# RATS_Schematic.net
KiCad netlist of a schematic drawn in EAGLE
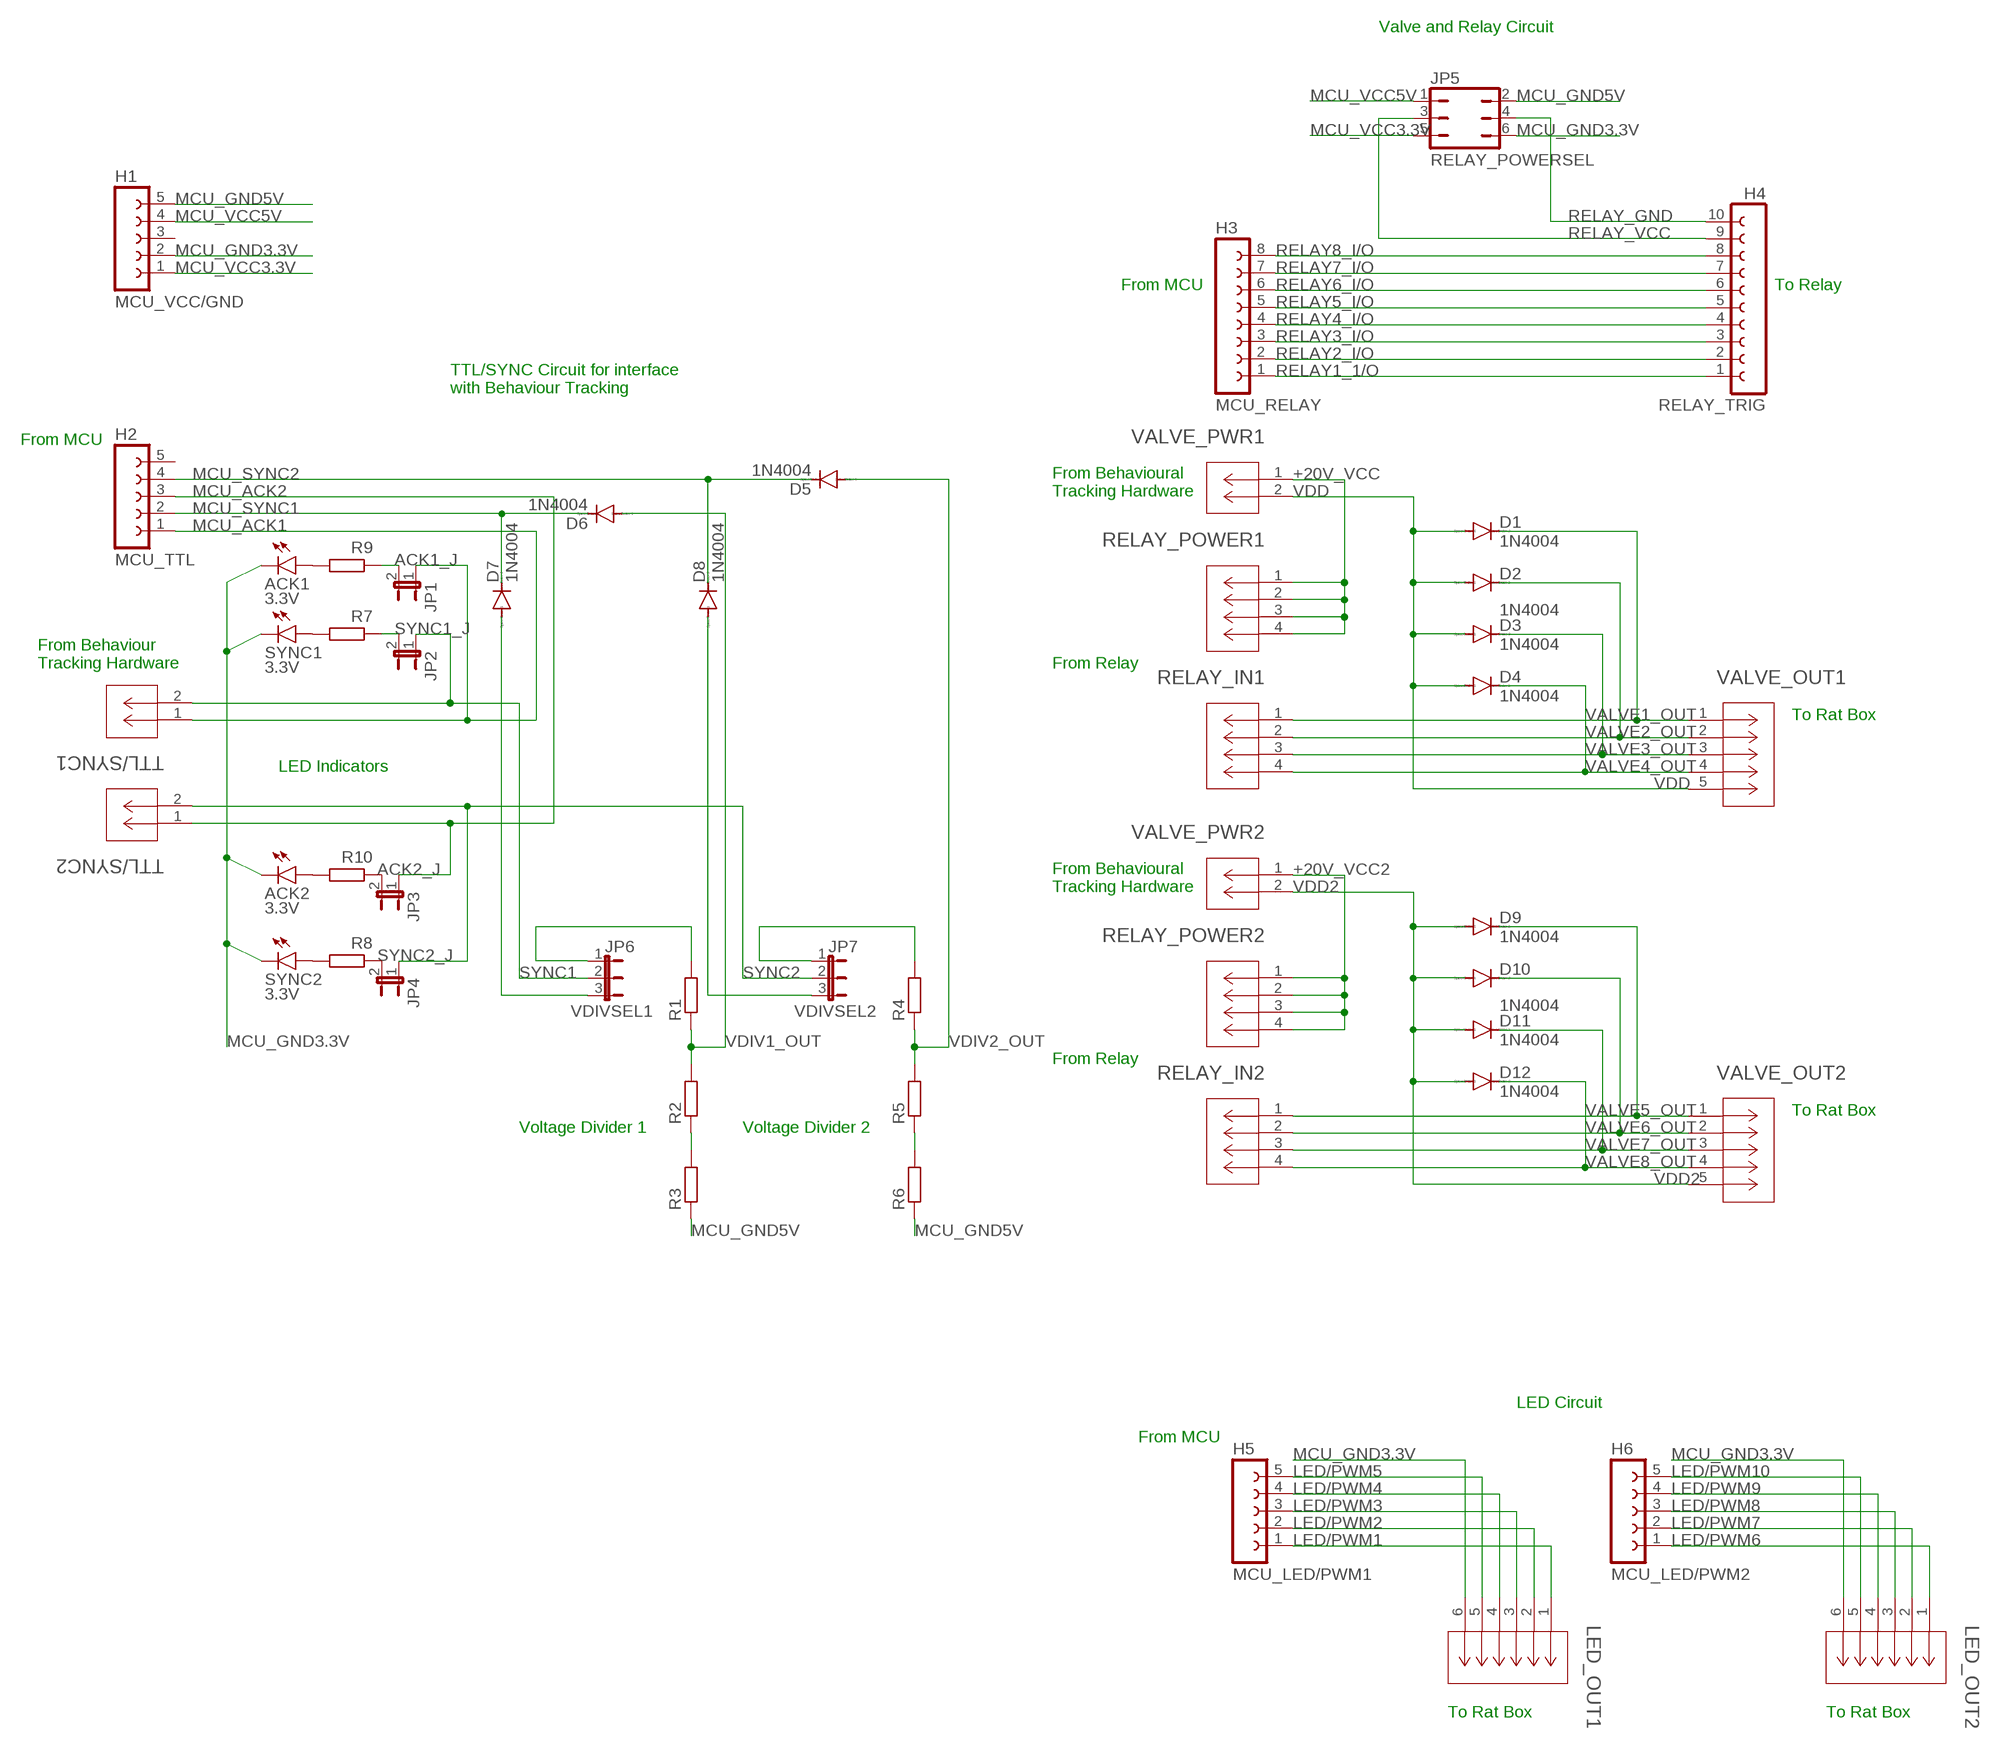
[diagram p0: schematic, sheet 1]

(export (version "E")
  (design (tool "Eeschema 10.0.6"))
  (components
    (comp (ref "ACK1")
      (value "3.3V")
      (footprint "eagle-import:LED5MM")
      (libsource (lib "eagle-import") (part "LED5MM"))
    )
    (comp (ref "ACK2")
      (value "3.3V")
      (footprint "eagle-import:LED5MM")
      (libsource (lib "eagle-import") (part "LED5MM"))
    )
    (comp (ref "D1")
      (value "1N4004")
      (footprint "eagle-import:DO41-10")
      (libsource (lib "eagle-import") (part "1N4004"))
    )
    (comp (ref "D2")
      (value "1N4004")
      (footprint "eagle-import:DO41-10")
      (libsource (lib "eagle-import") (part "1N4004"))
    )
    (comp (ref "D3")
      (value "1N4004")
      (footprint "eagle-import:DO41-10")
      (libsource (lib "eagle-import") (part "1N4004"))
    )
    (comp (ref "D4")
      (value "1N4004")
      (footprint "eagle-import:DO41-10")
      (libsource (lib "eagle-import") (part "1N4004"))
    )
    (comp (ref "D5")
      (value "1N4004")
      (footprint "eagle-import:DO41-10")
      (libsource (lib "eagle-import") (part "1N4004"))
    )
    (comp (ref "D6")
      (value "1N4004")
      (footprint "eagle-import:DO41-10")
      (libsource (lib "eagle-import") (part "1N4004"))
    )
    (comp (ref "D7")
      (value "1N4004")
      (footprint "eagle-import:DO41-10")
      (libsource (lib "eagle-import") (part "1N4004"))
    )
    (comp (ref "D8")
      (value "1N4004")
      (footprint "eagle-import:DO41-10")
      (libsource (lib "eagle-import") (part "1N4004"))
    )
    (comp (ref "D9")
      (value "1N4004")
      (footprint "eagle-import:DO41-10")
      (libsource (lib "eagle-import") (part "1N4004"))
    )
    (comp (ref "D10")
      (value "1N4004")
      (footprint "eagle-import:DO41-10")
      (libsource (lib "eagle-import") (part "1N4004"))
    )
    (comp (ref "D11")
      (value "1N4004")
      (footprint "eagle-import:DO41-10")
      (libsource (lib "eagle-import") (part "1N4004"))
    )
    (comp (ref "D12")
      (value "1N4004")
      (footprint "eagle-import:DO41-10")
      (libsource (lib "eagle-import") (part "1N4004"))
    )
    (comp (ref "H1")
      (value "MCU_VCC/GND")
      (footprint "eagle-import:FE05-1")
      (libsource (lib "eagle-import") (part "FE05-1"))
    )
    (comp (ref "H2")
      (value "MCU_TTL")
      (footprint "eagle-import:FE05-1")
      (libsource (lib "eagle-import") (part "FE05-1"))
    )
    (comp (ref "H3")
      (value "MCU_RELAY")
      (footprint "eagle-import:FE08")
      (libsource (lib "eagle-import") (part "FE08-1"))
    )
    (comp (ref "H4")
      (value "RELAY_TRIG")
      (footprint "eagle-import:FE10")
      (libsource (lib "eagle-import") (part "FE10-1"))
    )
    (comp (ref "H5")
      (value "MCU_LED/PWM1")
      (footprint "eagle-import:FE05-1")
      (libsource (lib "eagle-import") (part "FE05-1"))
    )
    (comp (ref "H6")
      (value "MCU_LED/PWM2")
      (footprint "eagle-import:FE05-1")
      (libsource (lib "eagle-import") (part "FE05-1"))
    )
    (comp (ref "JP1")
      (value "ACK1_J")
      (footprint "eagle-import:JP1")
      (libsource (lib "eagle-import") (part "JP1E"))
    )
    (comp (ref "JP2")
      (value "SYNC1_J")
      (footprint "eagle-import:JP1")
      (libsource (lib "eagle-import") (part "JP1E"))
    )
    (comp (ref "JP3")
      (value "ACK2_J")
      (footprint "eagle-import:JP1")
      (libsource (lib "eagle-import") (part "JP1E"))
    )
    (comp (ref "JP4")
      (value "SYNC2_J")
      (footprint "eagle-import:JP1")
      (libsource (lib "eagle-import") (part "JP1E"))
    )
    (comp (ref "JP5")
      (value "RELAY_POWERSEL")
      (footprint "eagle-import:JP3Q")
      (libsource (lib "eagle-import") (part "JP3Q"))
    )
    (comp (ref "JP6")
      (value "VDIVSEL1")
      (footprint "eagle-import:JP2")
      (libsource (lib "eagle-import") (part "JP2E"))
    )
    (comp (ref "JP7")
      (value "VDIVSEL2")
      (footprint "eagle-import:JP2")
      (libsource (lib "eagle-import") (part "JP2E"))
    )
    (comp (ref "LED_OUT1")
      (value "B6B-XH-A(LF)(SN)")
      (footprint "eagle-import:CONN_B6B-XH-A(LF)(SN)_JST")
      (fields (field (name "COPYRIGHT") "Copyright (C) 2021 Ultra Librarian. All rights reserved."))
      (libsource (lib "eagle-import") (part "B6B-XH-A(LF)(SN)"))
    )
    (comp (ref "LED_OUT2")
      (value "B6B-XH-A(LF)(SN)")
      (footprint "eagle-import:CONN_B6B-XH-A(LF)(SN)_JST")
      (fields (field (name "COPYRIGHT") "Copyright (C) 2021 Ultra Librarian. All rights reserved."))
      (libsource (lib "eagle-import") (part "B6B-XH-A(LF)(SN)"))
    )
    (comp (ref "R1")
      (value "R-EU_0204/7")
      (footprint "eagle-import:0204_7")
      (libsource (lib "eagle-import") (part "R-EU_0204/7"))
    )
    (comp (ref "R2")
      (value "R-EU_0204/7")
      (footprint "eagle-import:0204_7")
      (libsource (lib "eagle-import") (part "R-EU_0204/7"))
    )
    (comp (ref "R3")
      (value "R-EU_0204/7")
      (footprint "eagle-import:0204_7")
      (libsource (lib "eagle-import") (part "R-EU_0204/7"))
    )
    (comp (ref "R4")
      (value "R-EU_0204/7")
      (footprint "eagle-import:0204_7")
      (libsource (lib "eagle-import") (part "R-EU_0204/7"))
    )
    (comp (ref "R5")
      (value "R-EU_0204/7")
      (footprint "eagle-import:0204_7")
      (libsource (lib "eagle-import") (part "R-EU_0204/7"))
    )
    (comp (ref "R6")
      (value "R-EU_0204/7")
      (footprint "eagle-import:0204_7")
      (libsource (lib "eagle-import") (part "R-EU_0204/7"))
    )
    (comp (ref "R7")
      (value "R-EU_0204/7")
      (footprint "eagle-import:0204_7")
      (libsource (lib "eagle-import") (part "R-EU_0204/7"))
    )
    (comp (ref "R8")
      (value "R-EU_0204/7")
      (footprint "eagle-import:0204_7")
      (libsource (lib "eagle-import") (part "R-EU_0204/7"))
    )
    (comp (ref "R9")
      (value "R-EU_0204/7")
      (footprint "eagle-import:0204_7")
      (libsource (lib "eagle-import") (part "R-EU_0204/7"))
    )
    (comp (ref "R10")
      (value "R-EU_0204/7")
      (footprint "eagle-import:0204_7")
      (libsource (lib "eagle-import") (part "R-EU_0204/7"))
    )
    (comp (ref "RELAY_IN1")
      (value "B4B-XH-A_(LF)(SN)")
      (footprint "eagle-import:CONN_B4B-XH-A_(LF)(SN)_JST")
      (fields
        (field (name "MANUFACTURER_PART_NUMBER") "B4B-XH-A (LF)(SN)")
        (field (name "COPYRIGHT") "Copyright (C) 2021 Ultra Librarian. All rights reserved.")
      )
      (libsource (lib "eagle-import") (part "B4B-XH-A_(LF)(SN)"))
    )
    (comp (ref "RELAY_IN2")
      (value "B4B-XH-A_(LF)(SN)")
      (footprint "eagle-import:CONN_B4B-XH-A_(LF)(SN)_JST")
      (fields
        (field (name "MANUFACTURER_PART_NUMBER") "B4B-XH-A (LF)(SN)")
        (field (name "COPYRIGHT") "Copyright (C) 2021 Ultra Librarian. All rights reserved.")
      )
      (libsource (lib "eagle-import") (part "B4B-XH-A_(LF)(SN)"))
    )
    (comp (ref "RELAY_POWER1")
      (value "B4B-XH-A_(LF)(SN)")
      (footprint "eagle-import:CONN_B4B-XH-A_(LF)(SN)_JST")
      (fields
        (field (name "MANUFACTURER_PART_NUMBER") "B4B-XH-A (LF)(SN)")
        (field (name "COPYRIGHT") "Copyright (C) 2021 Ultra Librarian. All rights reserved.")
      )
      (libsource (lib "eagle-import") (part "B4B-XH-A_(LF)(SN)"))
    )
    (comp (ref "RELAY_POWER2")
      (value "B4B-XH-A_(LF)(SN)")
      (footprint "eagle-import:CONN_B4B-XH-A_(LF)(SN)_JST")
      (fields
        (field (name "MANUFACTURER_PART_NUMBER") "B4B-XH-A (LF)(SN)")
        (field (name "COPYRIGHT") "Copyright (C) 2021 Ultra Librarian. All rights reserved.")
      )
      (libsource (lib "eagle-import") (part "B4B-XH-A_(LF)(SN)"))
    )
    (comp (ref "SYNC1")
      (value "3.3V")
      (footprint "eagle-import:LED5MM")
      (libsource (lib "eagle-import") (part "LED5MM"))
    )
    (comp (ref "SYNC2")
      (value "3.3V")
      (footprint "eagle-import:LED5MM")
      (libsource (lib "eagle-import") (part "LED5MM"))
    )
    (comp (ref "TTL/SYNC1")
      (value "B2B-XH-A(LF)(SN)")
      (footprint "eagle-import:CONN_B2B-XH-A(LF)(SN)_JST")
      (fields (field (name "COPYRIGHT") "Copyright (C) 2021 Ultra Librarian. All rights reserved."))
      (libsource (lib "eagle-import") (part "B2B-XH-A(LF)(SN)"))
    )
    (comp (ref "TTL/SYNC2")
      (value "B2B-XH-A(LF)(SN)")
      (footprint "eagle-import:CONN_B2B-XH-A(LF)(SN)_JST")
      (fields (field (name "COPYRIGHT") "Copyright (C) 2021 Ultra Librarian. All rights reserved."))
      (libsource (lib "eagle-import") (part "B2B-XH-A(LF)(SN)"))
    )
    (comp (ref "VALVE_OUT1")
      (value "B5B-XH-A(LF)(SN)")
      (footprint "eagle-import:CONN_B5B-XH-A(LF)(SN)_JST")
      (fields (field (name "COPYRIGHT") "Copyright (C) 2021 Ultra Librarian. All rights reserved."))
      (libsource (lib "eagle-import") (part "B5B-XH-A(LF)(SN)"))
    )
    (comp (ref "VALVE_OUT2")
      (value "B5B-XH-A(LF)(SN)")
      (footprint "eagle-import:CONN_B5B-XH-A(LF)(SN)_JST")
      (fields (field (name "COPYRIGHT") "Copyright (C) 2021 Ultra Librarian. All rights reserved."))
      (libsource (lib "eagle-import") (part "B5B-XH-A(LF)(SN)"))
    )
    (comp (ref "VALVE_PWR1")
      (value "B2B-XH-A(LF)(SN)")
      (footprint "eagle-import:CONN_B2B-XH-A(LF)(SN)_JST")
      (fields (field (name "COPYRIGHT") "Copyright (C) 2021 Ultra Librarian. All rights reserved."))
      (libsource (lib "eagle-import") (part "B2B-XH-A(LF)(SN)"))
    )
    (comp (ref "VALVE_PWR2")
      (value "B2B-XH-A(LF)(SN)")
      (footprint "eagle-import:CONN_B2B-XH-A(LF)(SN)_JST")
      (fields (field (name "COPYRIGHT") "Copyright (C) 2021 Ultra Librarian. All rights reserved."))
      (libsource (lib "eagle-import") (part "B2B-XH-A(LF)(SN)"))
    )
  )
  (nets
    (net (code "1") (name "/+20V_VCC") (class "Default")
      (node (ref "RELAY_POWER1") (pin "1") (pinfunction "1_1") (pintype "passive"))
      (node (ref "RELAY_POWER1") (pin "2") (pinfunction "2_2") (pintype "passive"))
      (node (ref "RELAY_POWER1") (pin "3") (pinfunction "3_3") (pintype "passive"))
      (node (ref "RELAY_POWER1") (pin "4") (pinfunction "4_4") (pintype "passive"))
      (node (ref "VALVE_PWR1") (pin "1") (pinfunction "1_1") (pintype "passive"))
    )
    (net (code "2") (name "/+20V_VCC2") (class "Default")
      (node (ref "RELAY_POWER2") (pin "1") (pinfunction "1_1") (pintype "passive"))
      (node (ref "RELAY_POWER2") (pin "2") (pinfunction "2_2") (pintype "passive"))
      (node (ref "RELAY_POWER2") (pin "3") (pinfunction "3_3") (pintype "passive"))
      (node (ref "RELAY_POWER2") (pin "4") (pinfunction "4_4") (pintype "passive"))
      (node (ref "VALVE_PWR2") (pin "1") (pinfunction "1_1") (pintype "passive"))
    )
    (net (code "3") (name "/LED{slash}PWM1") (class "Default")
      (node (ref "H5") (pin "1") (pinfunction "1_1") (pintype "passive"))
      (node (ref "LED_OUT1") (pin "1") (pinfunction "1_1") (pintype "passive"))
    )
    (net (code "4") (name "/LED{slash}PWM2") (class "Default")
      (node (ref "H5") (pin "2") (pinfunction "2_2") (pintype "passive"))
      (node (ref "LED_OUT1") (pin "2") (pinfunction "2_2") (pintype "passive"))
    )
    (net (code "5") (name "/LED{slash}PWM3") (class "Default")
      (node (ref "H5") (pin "3") (pinfunction "3_3") (pintype "passive"))
      (node (ref "LED_OUT1") (pin "3") (pinfunction "3_3") (pintype "passive"))
    )
    (net (code "6") (name "/LED{slash}PWM4") (class "Default")
      (node (ref "H5") (pin "4") (pinfunction "4_4") (pintype "passive"))
      (node (ref "LED_OUT1") (pin "4") (pinfunction "4_4") (pintype "passive"))
    )
    (net (code "7") (name "/LED{slash}PWM5") (class "Default")
      (node (ref "H5") (pin "5") (pinfunction "5_5") (pintype "passive"))
      (node (ref "LED_OUT1") (pin "5") (pinfunction "5_5") (pintype "passive"))
    )
    (net (code "8") (name "/LED{slash}PWM6") (class "Default")
      (node (ref "H6") (pin "1") (pinfunction "1_1") (pintype "passive"))
      (node (ref "LED_OUT2") (pin "1") (pinfunction "1_1") (pintype "passive"))
    )
    (net (code "9") (name "/LED{slash}PWM7") (class "Default")
      (node (ref "H6") (pin "2") (pinfunction "2_2") (pintype "passive"))
      (node (ref "LED_OUT2") (pin "2") (pinfunction "2_2") (pintype "passive"))
    )
    (net (code "10") (name "/LED{slash}PWM8") (class "Default")
      (node (ref "H6") (pin "3") (pinfunction "3_3") (pintype "passive"))
      (node (ref "LED_OUT2") (pin "3") (pinfunction "3_3") (pintype "passive"))
    )
    (net (code "11") (name "/LED{slash}PWM9") (class "Default")
      (node (ref "H6") (pin "4") (pinfunction "4_4") (pintype "passive"))
      (node (ref "LED_OUT2") (pin "4") (pinfunction "4_4") (pintype "passive"))
    )
    (net (code "12") (name "/LED{slash}PWM10") (class "Default")
      (node (ref "H6") (pin "5") (pinfunction "5_5") (pintype "passive"))
      (node (ref "LED_OUT2") (pin "5") (pinfunction "5_5") (pintype "passive"))
    )
    (net (code "13") (name "/MCU_ACK1") (class "Default")
      (node (ref "H2") (pin "1") (pinfunction "1_1") (pintype "passive"))
      (node (ref "JP1") (pin "1") (pinfunction "1_1") (pintype "passive"))
      (node (ref "TTL/SYNC1") (pin "1") (pinfunction "1_1") (pintype "passive"))
    )
    (net (code "14") (name "/MCU_ACK2") (class "Default")
      (node (ref "H2") (pin "3") (pinfunction "3_3") (pintype "passive"))
      (node (ref "JP3") (pin "1") (pinfunction "1_1") (pintype "passive"))
      (node (ref "TTL/SYNC2") (pin "1") (pinfunction "1_1") (pintype "passive"))
    )
    (net (code "15") (name "/MCU_GND3.3V") (class "Default")
      (node (ref "ACK1") (pin "K") (pinfunction "C_K") (pintype "passive"))
      (node (ref "ACK2") (pin "K") (pinfunction "C_K") (pintype "passive"))
      (node (ref "H1") (pin "2") (pinfunction "2_2") (pintype "passive"))
      (node (ref "JP5") (pin "6") (pinfunction "6_6") (pintype "passive"))
      (node (ref "LED_OUT1") (pin "6") (pinfunction "6_6") (pintype "passive"))
      (node (ref "LED_OUT2") (pin "6") (pinfunction "6_6") (pintype "passive"))
      (node (ref "SYNC1") (pin "K") (pinfunction "C_K") (pintype "passive"))
      (node (ref "SYNC2") (pin "K") (pinfunction "C_K") (pintype "passive"))
    )
    (net (code "16") (name "/MCU_GND5V") (class "Default")
      (node (ref "H1") (pin "5") (pinfunction "5_5") (pintype "passive"))
      (node (ref "JP5") (pin "2") (pinfunction "2_2") (pintype "passive"))
      (node (ref "R3") (pin "1") (pinfunction "1_1") (pintype "passive"))
      (node (ref "R6") (pin "1") (pinfunction "1_1") (pintype "passive"))
    )
    (net (code "17") (name "/MCU_SYNC1") (class "Default")
      (node (ref "D6") (pin "C") (pinfunction "C_C") (pintype "passive"))
      (node (ref "D7") (pin "C") (pinfunction "C_C") (pintype "passive"))
      (node (ref "H2") (pin "2") (pinfunction "2_2") (pintype "passive"))
    )
    (net (code "18") (name "/MCU_SYNC2") (class "Default")
      (node (ref "D5") (pin "C") (pinfunction "C_C") (pintype "passive"))
      (node (ref "D8") (pin "C") (pinfunction "C_C") (pintype "passive"))
      (node (ref "H2") (pin "4") (pinfunction "4_4") (pintype "passive"))
    )
    (net (code "19") (name "/MCU_VCC3.3V") (class "Default")
      (node (ref "H1") (pin "1") (pinfunction "1_1") (pintype "passive"))
      (node (ref "JP5") (pin "5") (pinfunction "5_5") (pintype "passive"))
    )
    (net (code "20") (name "/MCU_VCC5V") (class "Default")
      (node (ref "H1") (pin "4") (pinfunction "4_4") (pintype "passive"))
      (node (ref "JP5") (pin "1") (pinfunction "1_1") (pintype "passive"))
    )
    (net (code "21") (name "/RELAY1_1{slash}O") (class "Default")
      (node (ref "H3") (pin "1") (pinfunction "1_1") (pintype "passive"))
      (node (ref "H4") (pin "1") (pinfunction "1_1") (pintype "passive"))
    )
    (net (code "22") (name "/RELAY2_I{slash}O") (class "Default")
      (node (ref "H3") (pin "2") (pinfunction "2_2") (pintype "passive"))
      (node (ref "H4") (pin "2") (pinfunction "2_2") (pintype "passive"))
    )
    (net (code "23") (name "/RELAY3_I{slash}O") (class "Default")
      (node (ref "H3") (pin "3") (pinfunction "3_3") (pintype "passive"))
      (node (ref "H4") (pin "3") (pinfunction "3_3") (pintype "passive"))
    )
    (net (code "24") (name "/RELAY4_I{slash}O") (class "Default")
      (node (ref "H3") (pin "4") (pinfunction "4_4") (pintype "passive"))
      (node (ref "H4") (pin "4") (pinfunction "4_4") (pintype "passive"))
    )
    (net (code "25") (name "/RELAY5_I{slash}O") (class "Default")
      (node (ref "H3") (pin "5") (pinfunction "5_5") (pintype "passive"))
      (node (ref "H4") (pin "5") (pinfunction "5_5") (pintype "passive"))
    )
    (net (code "26") (name "/RELAY6_I{slash}O") (class "Default")
      (node (ref "H3") (pin "6") (pinfunction "6_6") (pintype "passive"))
      (node (ref "H4") (pin "6") (pinfunction "6_6") (pintype "passive"))
    )
    (net (code "27") (name "/RELAY7_I{slash}O") (class "Default")
      (node (ref "H3") (pin "7") (pinfunction "7_7") (pintype "passive"))
      (node (ref "H4") (pin "7") (pinfunction "7_7") (pintype "passive"))
    )
    (net (code "28") (name "/RELAY8_I{slash}O") (class "Default")
      (node (ref "H3") (pin "8") (pinfunction "8_8") (pintype "passive"))
      (node (ref "H4") (pin "8") (pinfunction "8_8") (pintype "passive"))
    )
    (net (code "29") (name "/RELAY_GND") (class "Default")
      (node (ref "H4") (pin "10") (pinfunction "10_10") (pintype "passive"))
      (node (ref "JP5") (pin "4") (pinfunction "4_4") (pintype "passive"))
    )
    (net (code "30") (name "/RELAY_VCC") (class "Default")
      (node (ref "H4") (pin "9") (pinfunction "9_9") (pintype "passive"))
      (node (ref "JP5") (pin "3") (pinfunction "3_3") (pintype "passive"))
    )
    (net (code "31") (name "/SYNC1") (class "Default")
      (node (ref "JP2") (pin "1") (pinfunction "1_1") (pintype "passive"))
      (node (ref "JP6") (pin "2") (pinfunction "2_2") (pintype "passive"))
      (node (ref "TTL/SYNC1") (pin "2") (pinfunction "2_2") (pintype "passive"))
    )
    (net (code "32") (name "/SYNC2") (class "Default")
      (node (ref "JP4") (pin "1") (pinfunction "1_1") (pintype "passive"))
      (node (ref "JP7") (pin "2") (pinfunction "2_2") (pintype "passive"))
      (node (ref "TTL/SYNC2") (pin "2") (pinfunction "2_2") (pintype "passive"))
    )
    (net (code "33") (name "/VALVE1_OUT") (class "Default")
      (node (ref "D1") (pin "C") (pinfunction "C_C") (pintype "passive"))
      (node (ref "RELAY_IN1") (pin "1") (pinfunction "1_1") (pintype "passive"))
      (node (ref "VALVE_OUT1") (pin "1") (pinfunction "1_1") (pintype "passive"))
    )
    (net (code "34") (name "/VALVE2_OUT") (class "Default")
      (node (ref "D2") (pin "C") (pinfunction "C_C") (pintype "passive"))
      (node (ref "RELAY_IN1") (pin "2") (pinfunction "2_2") (pintype "passive"))
      (node (ref "VALVE_OUT1") (pin "2") (pinfunction "2_2") (pintype "passive"))
    )
    (net (code "35") (name "/VALVE3_OUT") (class "Default")
      (node (ref "D3") (pin "C") (pinfunction "C_C") (pintype "passive"))
      (node (ref "RELAY_IN1") (pin "3") (pinfunction "3_3") (pintype "passive"))
      (node (ref "VALVE_OUT1") (pin "3") (pinfunction "3_3") (pintype "passive"))
    )
    (net (code "36") (name "/VALVE4_OUT") (class "Default")
      (node (ref "D4") (pin "C") (pinfunction "C_C") (pintype "passive"))
      (node (ref "RELAY_IN1") (pin "4") (pinfunction "4_4") (pintype "passive"))
      (node (ref "VALVE_OUT1") (pin "4") (pinfunction "4_4") (pintype "passive"))
    )
    (net (code "37") (name "/VALVE5_OUT") (class "Default")
      (node (ref "D9") (pin "C") (pinfunction "C_C") (pintype "passive"))
      (node (ref "RELAY_IN2") (pin "1") (pinfunction "1_1") (pintype "passive"))
      (node (ref "VALVE_OUT2") (pin "1") (pinfunction "1_1") (pintype "passive"))
    )
    (net (code "38") (name "/VALVE6_OUT") (class "Default")
      (node (ref "D10") (pin "C") (pinfunction "C_C") (pintype "passive"))
      (node (ref "RELAY_IN2") (pin "2") (pinfunction "2_2") (pintype "passive"))
      (node (ref "VALVE_OUT2") (pin "2") (pinfunction "2_2") (pintype "passive"))
    )
    (net (code "39") (name "/VALVE7_OUT") (class "Default")
      (node (ref "D11") (pin "C") (pinfunction "C_C") (pintype "passive"))
      (node (ref "RELAY_IN2") (pin "3") (pinfunction "3_3") (pintype "passive"))
      (node (ref "VALVE_OUT2") (pin "3") (pinfunction "3_3") (pintype "passive"))
    )
    (net (code "40") (name "/VALVE8_OUT") (class "Default")
      (node (ref "D12") (pin "C") (pinfunction "C_C") (pintype "passive"))
      (node (ref "RELAY_IN2") (pin "4") (pinfunction "4_4") (pintype "passive"))
      (node (ref "VALVE_OUT2") (pin "4") (pinfunction "4_4") (pintype "passive"))
    )
    (net (code "41") (name "/VDD") (class "Default")
      (node (ref "D1") (pin "A") (pinfunction "A_A") (pintype "passive"))
      (node (ref "D2") (pin "A") (pinfunction "A_A") (pintype "passive"))
      (node (ref "D3") (pin "A") (pinfunction "A_A") (pintype "passive"))
      (node (ref "D4") (pin "A") (pinfunction "A_A") (pintype "passive"))
      (node (ref "VALVE_OUT1") (pin "5") (pinfunction "5_5") (pintype "passive"))
      (node (ref "VALVE_PWR1") (pin "2") (pinfunction "2_2") (pintype "passive"))
    )
    (net (code "42") (name "/VDD2") (class "Default")
      (node (ref "D10") (pin "A") (pinfunction "A_A") (pintype "passive"))
      (node (ref "D11") (pin "A") (pinfunction "A_A") (pintype "passive"))
      (node (ref "D12") (pin "A") (pinfunction "A_A") (pintype "passive"))
      (node (ref "D9") (pin "A") (pinfunction "A_A") (pintype "passive"))
      (node (ref "VALVE_OUT2") (pin "5") (pinfunction "5_5") (pintype "passive"))
      (node (ref "VALVE_PWR2") (pin "2") (pinfunction "2_2") (pintype "passive"))
    )
    (net (code "43") (name "/VDIV1_OUT") (class "Default")
      (node (ref "D6") (pin "A") (pinfunction "A_A") (pintype "passive"))
      (node (ref "R1") (pin "1") (pinfunction "1_1") (pintype "passive"))
      (node (ref "R2") (pin "2") (pinfunction "2_2") (pintype "passive"))
    )
    (net (code "44") (name "/VDIV2_OUT") (class "Default")
      (node (ref "D5") (pin "A") (pinfunction "A_A") (pintype "passive"))
      (node (ref "R4") (pin "1") (pinfunction "1_1") (pintype "passive"))
      (node (ref "R5") (pin "2") (pinfunction "2_2") (pintype "passive"))
    )
    (net (code "45") (name "Net-(ACK1-PadA)") (class "Default")
      (node (ref "ACK1") (pin "A") (pinfunction "A_A") (pintype "passive"))
      (node (ref "R9") (pin "2") (pinfunction "2_2") (pintype "passive"))
    )
    (net (code "46") (name "Net-(ACK2-PadA)") (class "Default")
      (node (ref "ACK2") (pin "A") (pinfunction "A_A") (pintype "passive"))
      (node (ref "R10") (pin "2") (pinfunction "2_2") (pintype "passive"))
    )
    (net (code "47") (name "Net-(D7-PadA)") (class "Default")
      (node (ref "D7") (pin "A") (pinfunction "A_A") (pintype "passive"))
      (node (ref "JP6") (pin "3") (pinfunction "3_3") (pintype "passive"))
    )
    (net (code "48") (name "Net-(D8-PadA)") (class "Default")
      (node (ref "D8") (pin "A") (pinfunction "A_A") (pintype "passive"))
      (node (ref "JP7") (pin "3") (pinfunction "3_3") (pintype "passive"))
    )
    (net (code "49") (name "Net-(JP1-Pad2)") (class "Default")
      (node (ref "JP1") (pin "2") (pinfunction "2_2") (pintype "passive"))
      (node (ref "R9") (pin "1") (pinfunction "1_1") (pintype "passive"))
    )
    (net (code "50") (name "Net-(JP2-Pad2)") (class "Default")
      (node (ref "JP2") (pin "2") (pinfunction "2_2") (pintype "passive"))
      (node (ref "R7") (pin "1") (pinfunction "1_1") (pintype "passive"))
    )
    (net (code "51") (name "Net-(JP3-Pad2)") (class "Default")
      (node (ref "JP3") (pin "2") (pinfunction "2_2") (pintype "passive"))
      (node (ref "R10") (pin "1") (pinfunction "1_1") (pintype "passive"))
    )
    (net (code "52") (name "Net-(JP4-Pad2)") (class "Default")
      (node (ref "JP4") (pin "2") (pinfunction "2_2") (pintype "passive"))
      (node (ref "R8") (pin "1") (pinfunction "1_1") (pintype "passive"))
    )
    (net (code "53") (name "Net-(JP6-Pad1)") (class "Default")
      (node (ref "JP6") (pin "1") (pinfunction "1_1") (pintype "passive"))
      (node (ref "R1") (pin "2") (pinfunction "2_2") (pintype "passive"))
    )
    (net (code "54") (name "Net-(JP7-Pad1)") (class "Default")
      (node (ref "JP7") (pin "1") (pinfunction "1_1") (pintype "passive"))
      (node (ref "R4") (pin "2") (pinfunction "2_2") (pintype "passive"))
    )
    (net (code "55") (name "Net-(R2-Pad1)") (class "Default")
      (node (ref "R2") (pin "1") (pinfunction "1_1") (pintype "passive"))
      (node (ref "R3") (pin "2") (pinfunction "2_2") (pintype "passive"))
    )
    (net (code "56") (name "Net-(R5-Pad1)") (class "Default")
      (node (ref "R5") (pin "1") (pinfunction "1_1") (pintype "passive"))
      (node (ref "R6") (pin "2") (pinfunction "2_2") (pintype "passive"))
    )
    (net (code "57") (name "Net-(R7-Pad2)") (class "Default")
      (node (ref "R7") (pin "2") (pinfunction "2_2") (pintype "passive"))
      (node (ref "SYNC1") (pin "A") (pinfunction "A_A") (pintype "passive"))
    )
    (net (code "58") (name "Net-(R8-Pad2)") (class "Default")
      (node (ref "R8") (pin "2") (pinfunction "2_2") (pintype "passive"))
      (node (ref "SYNC2") (pin "A") (pinfunction "A_A") (pintype "passive"))
    )
    (net (code "59") (name "unconnected-(H1-Pad3)") (class "Default")
      (node (ref "H1") (pin "3") (pinfunction "3_3") (pintype "passive"))
    )
    (net (code "60") (name "unconnected-(H2-Pad5)") (class "Default")
      (node (ref "H2") (pin "5") (pinfunction "5_5") (pintype "passive"))
    )
  )
)
